# EPS_Battery_Controller_Current-Meas.net
KiCad netlist of a schematic drawn in Altium Designer
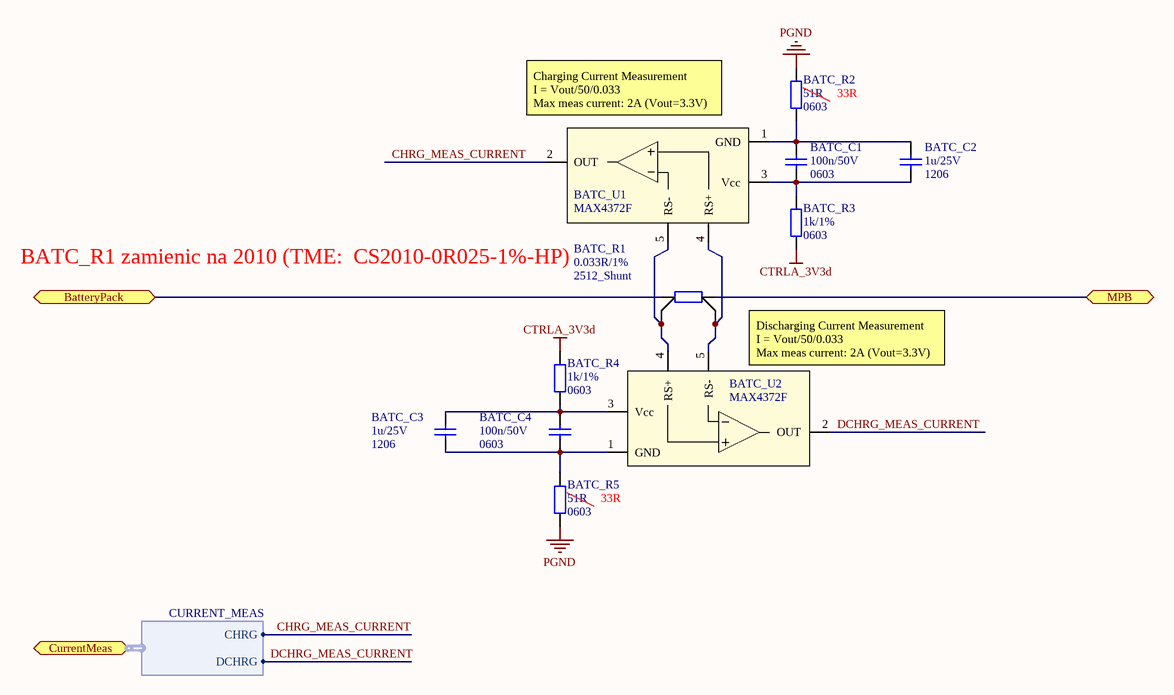
[diagram p0: EPS_Battery_Controller_Current-Meas.SchDoc]

(export (version "E")
  (design (tool "Eeschema 10.0.6"))
  (components
    (comp (ref "BATC_C1")
      (value "100n/50V")
      (footprint "SMD_Capacitor_0603")
      (description "Ceramic Cap Murata Automotive 100n/50V X7R 0603")
      (fields
        (field (name "MANUFACTURER") "Murata")
        (field (name "MANUFACTURERPARTNUMBER") "GCJ188R71H104KA12D")
        (field (name "PACKAGE") "0603")
      )
      (libsource (lib "capacitors") (part "Cer_GCJ188R71H104KA12D"))
    )
    (comp (ref "BATC_C2")
      (value "1u/25V")
      (footprint "SMD_Capacitor_1206")
      (description "Ceramic Cap Kemet COTS 1u/25V X7R 1206")
      (fields
        (field (name "MANUFACTURERPARTNUMBER") "C1206T105K3RALTU")
        (field (name "MANUFACTURER") "Kemet")
        (field (name "PACKAGE") "1206")
      )
      (libsource (lib "capacitors") (part "Cer_C1206T105K3RALTU"))
    )
    (comp (ref "BATC_C3")
      (value "1u/25V")
      (footprint "SMD_Capacitor_1206")
      (description "Ceramic Cap Kemet COTS 1u/25V X7R 1206")
      (fields
        (field (name "MANUFACTURERPARTNUMBER") "C1206T105K3RALTU")
        (field (name "MANUFACTURER") "Kemet")
        (field (name "PACKAGE") "1206")
      )
      (libsource (lib "capacitors") (part "Cer_C1206T105K3RALTU"))
    )
    (comp (ref "BATC_C4")
      (value "100n/50V")
      (footprint "SMD_Capacitor_0603")
      (description "Ceramic Cap Murata Automotive 100n/50V X7R 0603")
      (fields
        (field (name "MANUFACTURER") "Murata")
        (field (name "MANUFACTURERPARTNUMBER") "GCJ188R71H104KA12D")
        (field (name "PACKAGE") "0603")
      )
      (libsource (lib "capacitors") (part "Cer_GCJ188R71H104KA12D"))
    )
    (comp (ref "BATC_R1")
      (value "0.033R/1%")
      (footprint "SMD_Resistor-shunt_2512")
      (description "33mR ,1%, 2W, shunt resistor, TE Connectivity.")
      (fields
        (field (name "MANUFACTURERPARTNUMBER") "LR2512-R033FW")
        (field (name "MANUFACTURER") "TE Connectivity")
        (field (name "PACKAGE") "2512_Shunt")
      )
      (libsource (lib "resistors") (part "LR2512-R033FW"))
    )
    (comp (ref "BATC_R2")
      (value "51R")
      (footprint "SMD_Resistor_0603")
      (fields (field (name "PACKAGE") "0603"))
      (libsource (lib "resistors") (part "Res"))
    )
    (comp (ref "BATC_R3")
      (value "1k/1%")
      (footprint "SMD_Resistor_0603")
      (fields (field (name "PACKAGE") "0603"))
      (libsource (lib "resistors") (part "Res"))
    )
    (comp (ref "BATC_R4")
      (value "1k/1%")
      (footprint "SMD_Resistor_0603")
      (fields (field (name "PACKAGE") "0603"))
      (libsource (lib "") (part "Res_1"))
    )
    (comp (ref "BATC_R5")
      (value "51R")
      (footprint "SMD_Resistor_0603")
      (fields (field (name "PACKAGE") "0603"))
      (libsource (lib "resistors") (part "Res"))
    )
    (comp (ref "BATC_U1")
      (value "MAX4372F")
      (footprint "SOT23-5")
      (description "High-Side Current-Sense Amplifier with Voltage Output")
      (fields (field (name "MANUFACTURER") "Maxim Integrated Products"))
      (libsource (lib "") (part "MAX4372_1"))
    )
    (comp (ref "BATC_U2")
      (value "MAX4372F")
      (footprint "SOT23-5")
      (description "High-Side Current-Sense Amplifier with Voltage Output")
      (fields (field (name "MANUFACTURER") "Maxim Integrated Products"))
      (libsource (lib "microcircuits") (part "MAX4372"))
    )
  )
  (nets
    (net (code "2") (name "/BatteryPack") (class "Default")
      (node (ref "BATC_R1") (pin "1") (pinfunction "1_1") (pintype "passive"))
    )
    (net (code "3") (name "/CHRG_MEAS_CURRENT") (class "Default")
      (node (ref "BATC_U1") (pin "2") (pinfunction "OUT_2") (pintype "passive"))
    )
    (net (code "4") (name "/DCHRG_MEAS_CURRENT") (class "Default")
      (node (ref "BATC_U2") (pin "2") (pinfunction "OUT_2") (pintype "passive"))
    )
    (net (code "5") (name "/MPB") (class "Default")
      (node (ref "BATC_R1") (pin "4") (pinfunction "4_4") (pintype "passive"))
    )
    (net (code "7") (name "CTRLA_3V3d") (class "Default")
      (node (ref "BATC_R3") (pin "1") (pinfunction "1_1") (pintype "passive"))
      (node (ref "BATC_R4") (pin "1") (pinfunction "1_1") (pintype "passive"))
    )
    (net (code "8") (name "Net-(BATC_U1-GND)") (class "Default")
      (node (ref "BATC_C1") (pin "1") (pinfunction "1_1") (pintype "passive"))
      (node (ref "BATC_C2") (pin "1") (pinfunction "1_1") (pintype "passive"))
      (node (ref "BATC_R2") (pin "1") (pinfunction "1_1") (pintype "passive"))
      (node (ref "BATC_U1") (pin "1") (pinfunction "GND_1") (pintype "passive"))
    )
    (net (code "9") (name "Net-(BATC_U1-RS+)") (class "Default")
      (node (ref "BATC_R1") (pin "3") (pinfunction "3_3") (pintype "passive"))
      (node (ref "BATC_U1") (pin "4") (pinfunction "RS+_4") (pintype "passive"))
      (node (ref "BATC_U2") (pin "5") (pinfunction "RS-_5") (pintype "passive"))
    )
    (net (code "10") (name "Net-(BATC_U1-RS-)") (class "Default")
      (node (ref "BATC_R1") (pin "2") (pinfunction "2_2") (pintype "passive"))
      (node (ref "BATC_U1") (pin "5") (pinfunction "RS-_5") (pintype "passive"))
      (node (ref "BATC_U2") (pin "4") (pinfunction "RS+_4") (pintype "passive"))
    )
    (net (code "11") (name "Net-(BATC_U1-Vcc)") (class "Default")
      (node (ref "BATC_C1") (pin "2") (pinfunction "2_2") (pintype "passive"))
      (node (ref "BATC_C2") (pin "2") (pinfunction "2_2") (pintype "passive"))
      (node (ref "BATC_R3") (pin "2") (pinfunction "2_2") (pintype "passive"))
      (node (ref "BATC_U1") (pin "3") (pinfunction "Vcc_3") (pintype "passive"))
    )
    (net (code "12") (name "Net-(BATC_U2-GND)") (class "Default")
      (node (ref "BATC_C3") (pin "2") (pinfunction "2_2") (pintype "passive"))
      (node (ref "BATC_C4") (pin "2") (pinfunction "2_2") (pintype "passive"))
      (node (ref "BATC_R5") (pin "2") (pinfunction "2_2") (pintype "passive"))
      (node (ref "BATC_U2") (pin "1") (pinfunction "GND_1") (pintype "passive"))
    )
    (net (code "13") (name "Net-(BATC_U2-Vcc)") (class "Default")
      (node (ref "BATC_C3") (pin "1") (pinfunction "1_1") (pintype "passive"))
      (node (ref "BATC_C4") (pin "1") (pinfunction "1_1") (pintype "passive"))
      (node (ref "BATC_R4") (pin "2") (pinfunction "2_2") (pintype "passive"))
      (node (ref "BATC_U2") (pin "3") (pinfunction "Vcc_3") (pintype "passive"))
    )
    (net (code "14") (name "PGND") (class "Default")
      (node (ref "BATC_R2") (pin "2") (pinfunction "2_2") (pintype "passive"))
      (node (ref "BATC_R5") (pin "1") (pinfunction "1_1") (pintype "passive"))
    )
  )
)
